# FY_-_OPTO_BOARD_4_IOX.net
KiCad netlist of a schematic drawn in EAGLE
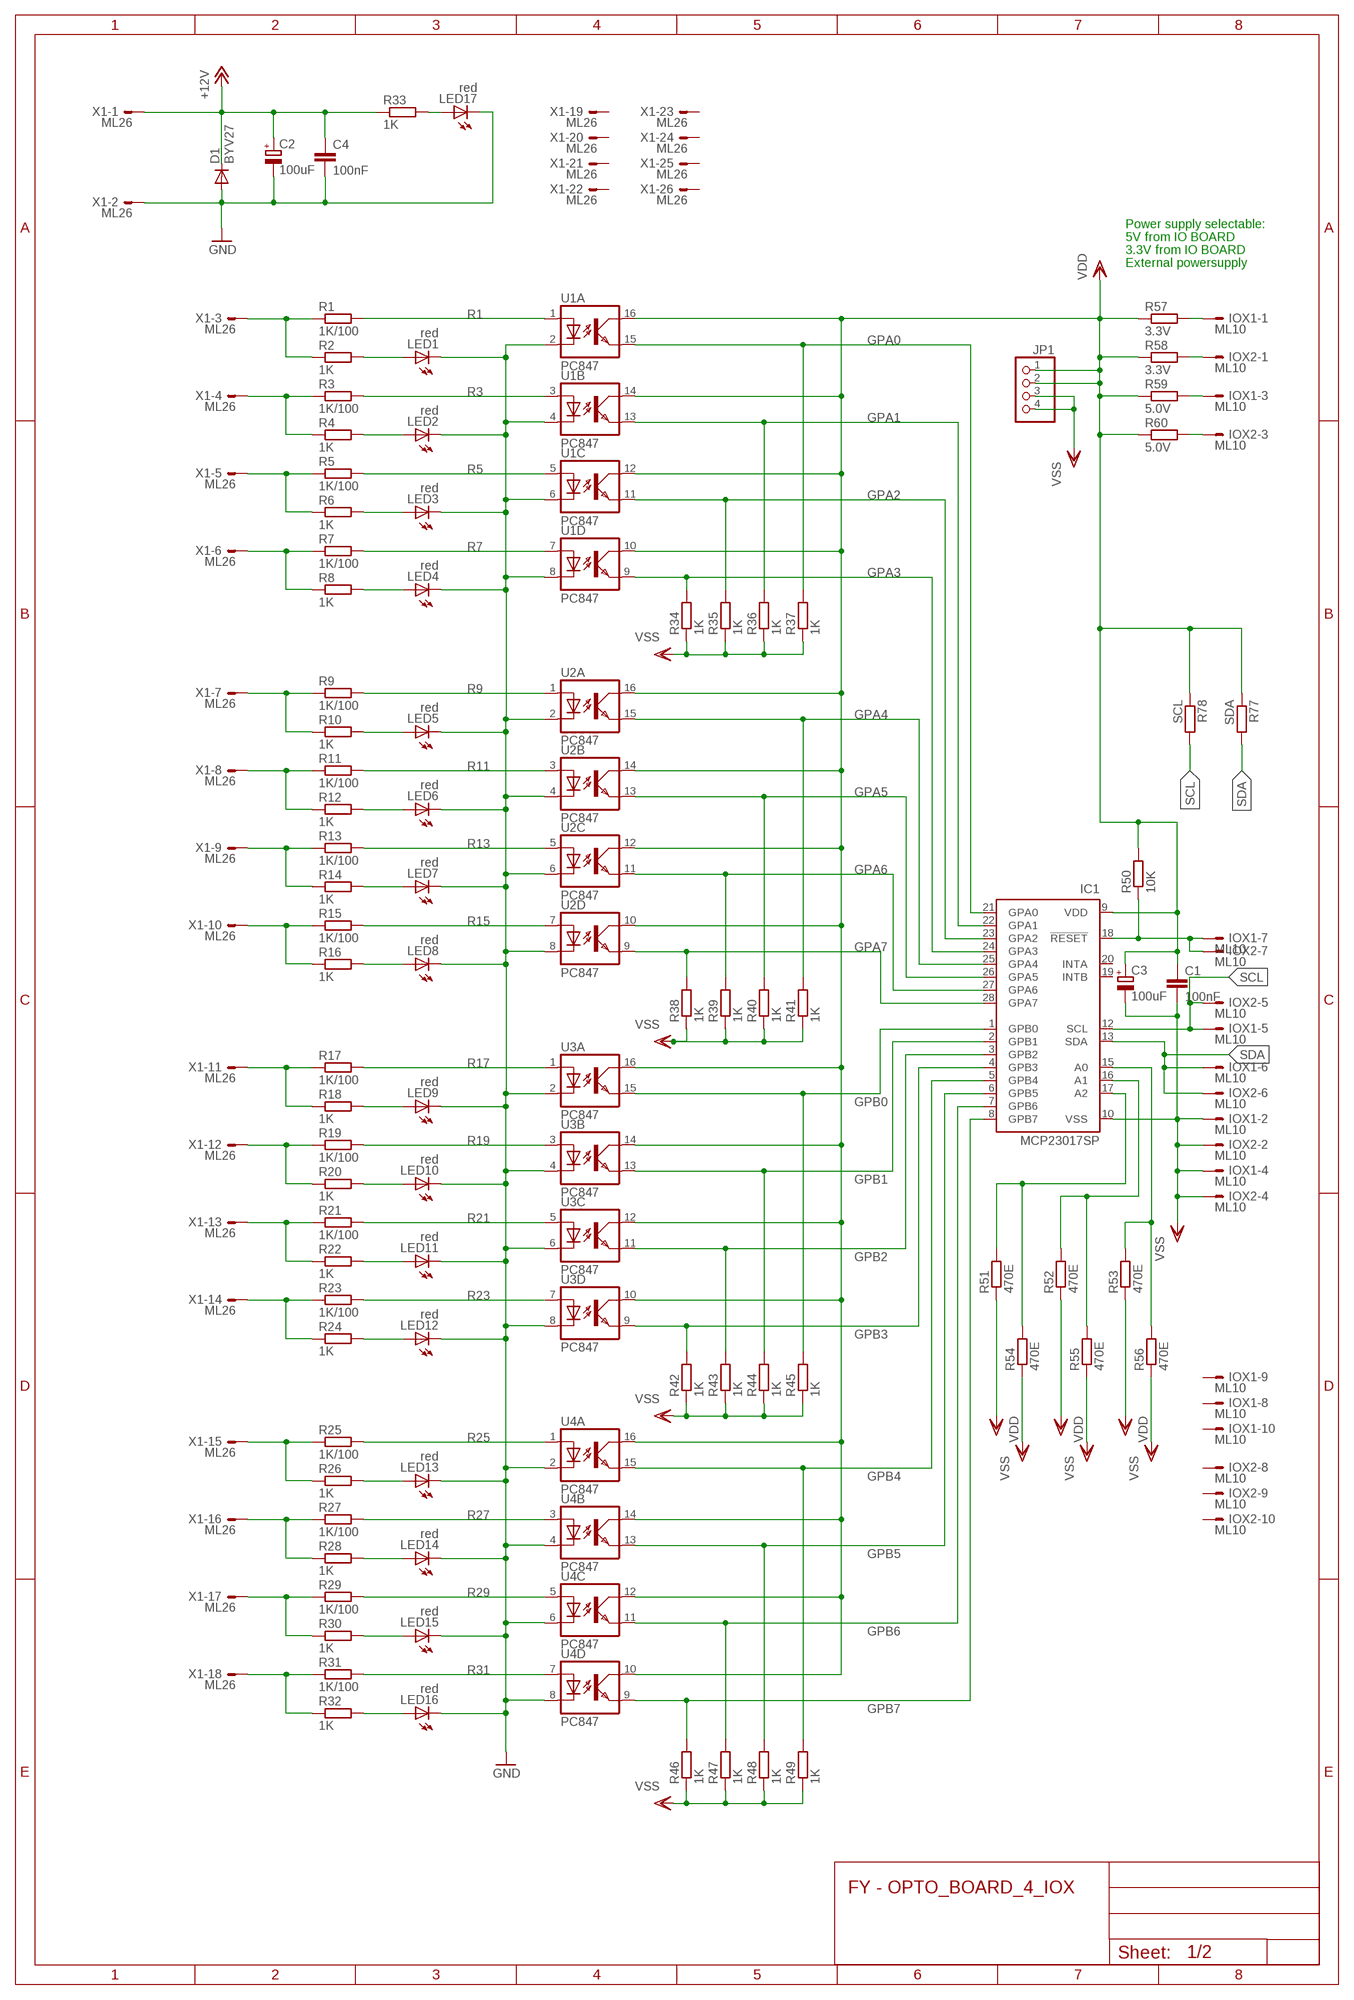
[diagram p0: schematic, sheet 1]
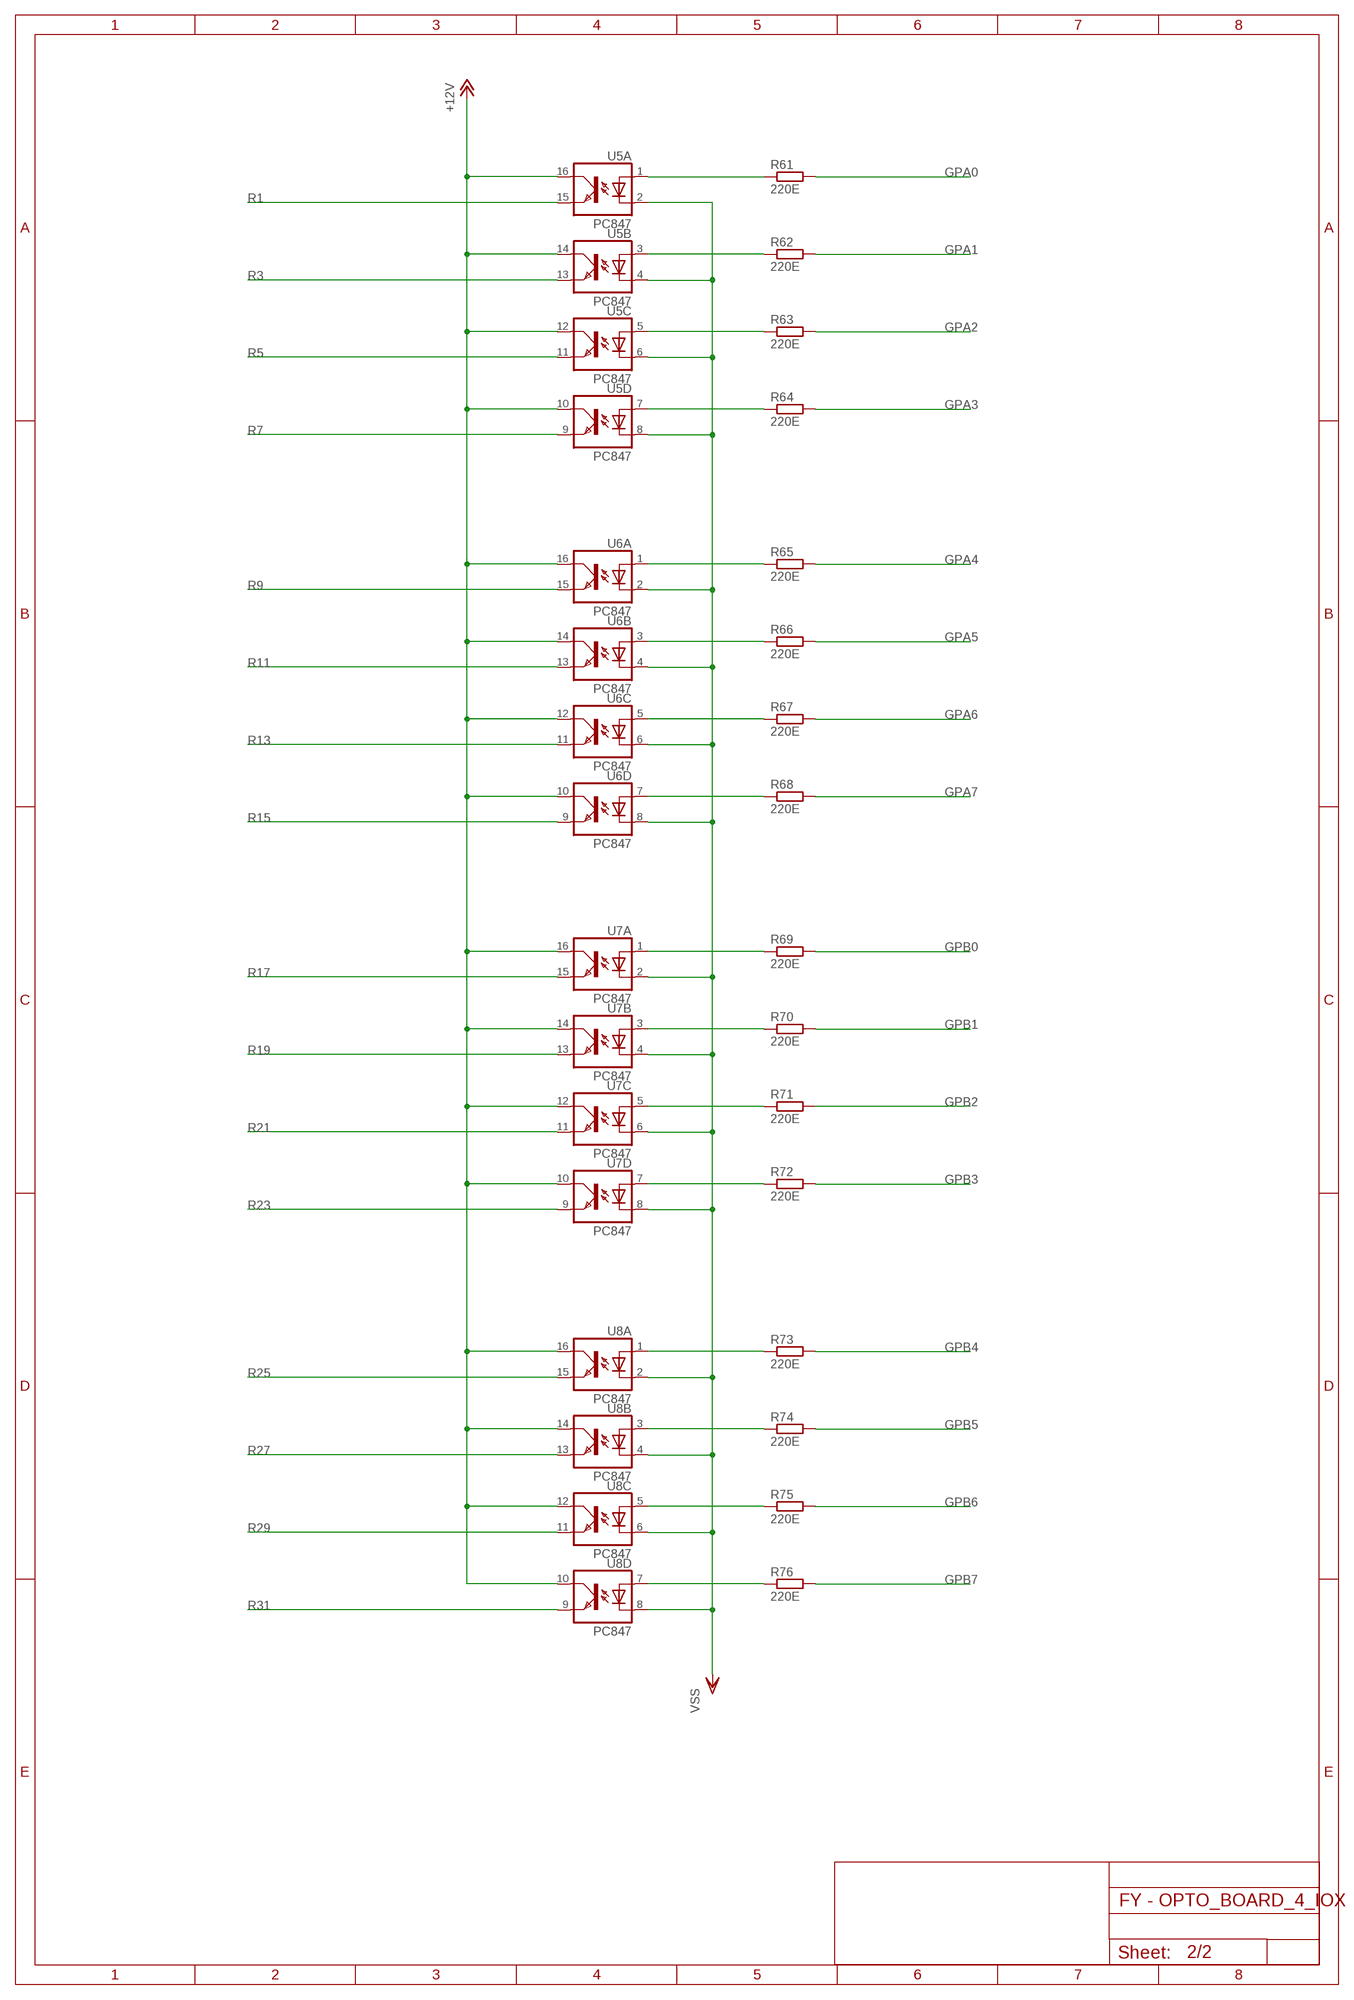
[diagram p1: schematic, sheet 2]

(export (version "E")
  (design (tool "Eeschema 10.0.6"))
  (components
    (comp (ref "R61")
      (value "220E")
      (footprint "eagle-import:0207_10")
      (libsource (lib "eagle-import") (part "R-EU_0207/10"))
    )
    (comp (ref "R62")
      (value "220E")
      (footprint "eagle-import:0207_10")
      (libsource (lib "eagle-import") (part "R-EU_0207/10"))
    )
    (comp (ref "R63")
      (value "220E")
      (footprint "eagle-import:0207_10")
      (libsource (lib "eagle-import") (part "R-EU_0207/10"))
    )
    (comp (ref "R64")
      (value "220E")
      (footprint "eagle-import:0207_10")
      (libsource (lib "eagle-import") (part "R-EU_0207/10"))
    )
    (comp (ref "R65")
      (value "220E")
      (footprint "eagle-import:0207_10")
      (libsource (lib "eagle-import") (part "R-EU_0207/10"))
    )
    (comp (ref "R66")
      (value "220E")
      (footprint "eagle-import:0207_10")
      (libsource (lib "eagle-import") (part "R-EU_0207/10"))
    )
    (comp (ref "R67")
      (value "220E")
      (footprint "eagle-import:0207_10")
      (libsource (lib "eagle-import") (part "R-EU_0207/10"))
    )
    (comp (ref "R68")
      (value "220E")
      (footprint "eagle-import:0207_10")
      (libsource (lib "eagle-import") (part "R-EU_0207/10"))
    )
    (comp (ref "R69")
      (value "220E")
      (footprint "eagle-import:0207_10")
      (libsource (lib "eagle-import") (part "R-EU_0207/10"))
    )
    (comp (ref "R70")
      (value "220E")
      (footprint "eagle-import:0207_10")
      (libsource (lib "eagle-import") (part "R-EU_0207/10"))
    )
    (comp (ref "R71")
      (value "220E")
      (footprint "eagle-import:0207_10")
      (libsource (lib "eagle-import") (part "R-EU_0207/10"))
    )
    (comp (ref "R72")
      (value "220E")
      (footprint "eagle-import:0207_10")
      (libsource (lib "eagle-import") (part "R-EU_0207/10"))
    )
    (comp (ref "R73")
      (value "220E")
      (footprint "eagle-import:0207_10")
      (libsource (lib "eagle-import") (part "R-EU_0207/10"))
    )
    (comp (ref "R74")
      (value "220E")
      (footprint "eagle-import:0207_10")
      (libsource (lib "eagle-import") (part "R-EU_0207/10"))
    )
    (comp (ref "R75")
      (value "220E")
      (footprint "eagle-import:0207_10")
      (libsource (lib "eagle-import") (part "R-EU_0207/10"))
    )
    (comp (ref "R76")
      (value "220E")
      (footprint "eagle-import:0207_10")
      (libsource (lib "eagle-import") (part "R-EU_0207/10"))
    )
    (comp (ref "U5")
      (value "PC847")
      (footprint "eagle-import:DIL16")
      (libsource (lib "eagle-import") (part "PC847"))
    )
    (comp (ref "U6")
      (value "PC847")
      (footprint "eagle-import:DIL16")
      (libsource (lib "eagle-import") (part "PC847"))
    )
    (comp (ref "U7")
      (value "PC847")
      (footprint "eagle-import:DIL16")
      (libsource (lib "eagle-import") (part "PC847"))
    )
    (comp (ref "U8")
      (value "PC847")
      (footprint "eagle-import:DIL16")
      (libsource (lib "eagle-import") (part "PC847"))
    )
    (comp (ref "C1")
      (value "100nF")
      (footprint "eagle-import:C050-025X075")
      (libsource (lib "eagle-import") (part "C-EU050-025X075"))
    )
    (comp (ref "C2")
      (value "100uF")
      (footprint "eagle-import:E5-8,5")
      (libsource (lib "eagle-import") (part "CPOL-EUE5-8.5"))
    )
    (comp (ref "C3")
      (value "100uF")
      (footprint "eagle-import:E5-8,5")
      (libsource (lib "eagle-import") (part "CPOL-EUE5-8.5"))
    )
    (comp (ref "C4")
      (value "100nF")
      (footprint "eagle-import:C050-025X075")
      (libsource (lib "eagle-import") (part "C-EU050-025X075"))
    )
    (comp (ref "D1")
      (value "BYV27")
      (footprint "eagle-import:SOD57-10")
      (libsource (lib "eagle-import") (part "BYV27"))
    )
    (comp (ref "IC1")
      (value "MCP23017SP")
      (footprint "eagle-import:DIL28-3")
      (fields (field (name "MF") "MICROCHIP") (field (name "MPN") "MCP23017-E/SP"))
      (libsource (lib "eagle-import") (part "MCP23017SP"))
    )
    (comp (ref "IOX1")
      (value "ML10")
      (footprint "eagle-import:ML10")
      (libsource (lib "eagle-import") (part "ML10?E"))
    )
    (comp (ref "IOX2")
      (value "ML10")
      (footprint "eagle-import:ML10")
      (libsource (lib "eagle-import") (part "ML10?E"))
    )
    (comp (ref "JP1")
      (value "PINHD-1X4")
      (footprint "eagle-import:1X04")
      (libsource (lib "eagle-import") (part "PINHD-1X4"))
    )
    (comp (ref "LED1")
      (value "red")
      (footprint "eagle-import:LED3MM")
      (libsource (lib "eagle-import") (part "LED3MM"))
    )
    (comp (ref "LED2")
      (value "red")
      (footprint "eagle-import:LED3MM")
      (libsource (lib "eagle-import") (part "LED3MM"))
    )
    (comp (ref "LED3")
      (value "red")
      (footprint "eagle-import:LED3MM")
      (libsource (lib "eagle-import") (part "LED3MM"))
    )
    (comp (ref "LED4")
      (value "red")
      (footprint "eagle-import:LED3MM")
      (libsource (lib "eagle-import") (part "LED3MM"))
    )
    (comp (ref "LED5")
      (value "red")
      (footprint "eagle-import:LED3MM")
      (libsource (lib "eagle-import") (part "LED3MM"))
    )
    (comp (ref "LED6")
      (value "red")
      (footprint "eagle-import:LED3MM")
      (libsource (lib "eagle-import") (part "LED3MM"))
    )
    (comp (ref "LED7")
      (value "red")
      (footprint "eagle-import:LED3MM")
      (libsource (lib "eagle-import") (part "LED3MM"))
    )
    (comp (ref "LED8")
      (value "red")
      (footprint "eagle-import:LED3MM")
      (libsource (lib "eagle-import") (part "LED3MM"))
    )
    (comp (ref "LED9")
      (value "red")
      (footprint "eagle-import:LED3MM")
      (libsource (lib "eagle-import") (part "LED3MM"))
    )
    (comp (ref "LED10")
      (value "red")
      (footprint "eagle-import:LED3MM")
      (libsource (lib "eagle-import") (part "LED3MM"))
    )
    (comp (ref "LED11")
      (value "red")
      (footprint "eagle-import:LED3MM")
      (libsource (lib "eagle-import") (part "LED3MM"))
    )
    (comp (ref "LED12")
      (value "red")
      (footprint "eagle-import:LED3MM")
      (libsource (lib "eagle-import") (part "LED3MM"))
    )
    (comp (ref "LED13")
      (value "red")
      (footprint "eagle-import:LED3MM")
      (libsource (lib "eagle-import") (part "LED3MM"))
    )
    (comp (ref "LED14")
      (value "red")
      (footprint "eagle-import:LED3MM")
      (libsource (lib "eagle-import") (part "LED3MM"))
    )
    (comp (ref "LED15")
      (value "red")
      (footprint "eagle-import:LED3MM")
      (libsource (lib "eagle-import") (part "LED3MM"))
    )
    (comp (ref "LED16")
      (value "red")
      (footprint "eagle-import:LED3MM")
      (libsource (lib "eagle-import") (part "LED3MM"))
    )
    (comp (ref "LED17")
      (value "red")
      (footprint "eagle-import:LED3MM")
      (libsource (lib "eagle-import") (part "LED3MM"))
    )
    (comp (ref "R1")
      (value "1K/100")
      (footprint "eagle-import:0207_10")
      (libsource (lib "eagle-import") (part "R-EU_0207/10"))
    )
    (comp (ref "R2")
      (value "1K")
      (footprint "eagle-import:0207_10")
      (libsource (lib "eagle-import") (part "R-EU_0207/10"))
    )
    (comp (ref "R3")
      (value "1K/100")
      (footprint "eagle-import:0207_10")
      (libsource (lib "eagle-import") (part "R-EU_0207/10"))
    )
    (comp (ref "R4")
      (value "1K")
      (footprint "eagle-import:0207_10")
      (libsource (lib "eagle-import") (part "R-EU_0207/10"))
    )
    (comp (ref "R5")
      (value "1K/100")
      (footprint "eagle-import:0207_10")
      (libsource (lib "eagle-import") (part "R-EU_0207/10"))
    )
    (comp (ref "R6")
      (value "1K")
      (footprint "eagle-import:0207_10")
      (libsource (lib "eagle-import") (part "R-EU_0207/10"))
    )
    (comp (ref "R7")
      (value "1K/100")
      (footprint "eagle-import:0207_10")
      (libsource (lib "eagle-import") (part "R-EU_0207/10"))
    )
    (comp (ref "R8")
      (value "1K")
      (footprint "eagle-import:0207_10")
      (libsource (lib "eagle-import") (part "R-EU_0207/10"))
    )
    (comp (ref "R9")
      (value "1K/100")
      (footprint "eagle-import:0207_10")
      (libsource (lib "eagle-import") (part "R-EU_0207/10"))
    )
    (comp (ref "R10")
      (value "1K")
      (footprint "eagle-import:0207_10")
      (libsource (lib "eagle-import") (part "R-EU_0207/10"))
    )
    (comp (ref "R11")
      (value "1K/100")
      (footprint "eagle-import:0207_10")
      (libsource (lib "eagle-import") (part "R-EU_0207/10"))
    )
    (comp (ref "R12")
      (value "1K")
      (footprint "eagle-import:0207_10")
      (libsource (lib "eagle-import") (part "R-EU_0207/10"))
    )
    (comp (ref "R13")
      (value "1K/100")
      (footprint "eagle-import:0207_10")
      (libsource (lib "eagle-import") (part "R-EU_0207/10"))
    )
    (comp (ref "R14")
      (value "1K")
      (footprint "eagle-import:0207_10")
      (libsource (lib "eagle-import") (part "R-EU_0207/10"))
    )
    (comp (ref "R15")
      (value "1K/100")
      (footprint "eagle-import:0207_10")
      (libsource (lib "eagle-import") (part "R-EU_0207/10"))
    )
    (comp (ref "R16")
      (value "1K")
      (footprint "eagle-import:0207_10")
      (libsource (lib "eagle-import") (part "R-EU_0207/10"))
    )
    (comp (ref "R17")
      (value "1K/100")
      (footprint "eagle-import:0207_10")
      (libsource (lib "eagle-import") (part "R-EU_0207/10"))
    )
    (comp (ref "R18")
      (value "1K")
      (footprint "eagle-import:0207_10")
      (libsource (lib "eagle-import") (part "R-EU_0207/10"))
    )
    (comp (ref "R19")
      (value "1K/100")
      (footprint "eagle-import:0207_10")
      (libsource (lib "eagle-import") (part "R-EU_0207/10"))
    )
    (comp (ref "R20")
      (value "1K")
      (footprint "eagle-import:0207_10")
      (libsource (lib "eagle-import") (part "R-EU_0207/10"))
    )
    (comp (ref "R21")
      (value "1K/100")
      (footprint "eagle-import:0207_10")
      (libsource (lib "eagle-import") (part "R-EU_0207/10"))
    )
    (comp (ref "R22")
      (value "1K")
      (footprint "eagle-import:0207_10")
      (libsource (lib "eagle-import") (part "R-EU_0207/10"))
    )
    (comp (ref "R23")
      (value "1K/100")
      (footprint "eagle-import:0207_10")
      (libsource (lib "eagle-import") (part "R-EU_0207/10"))
    )
    (comp (ref "R24")
      (value "1K")
      (footprint "eagle-import:0207_10")
      (libsource (lib "eagle-import") (part "R-EU_0207/10"))
    )
    (comp (ref "R25")
      (value "1K/100")
      (footprint "eagle-import:0207_10")
      (libsource (lib "eagle-import") (part "R-EU_0207/10"))
    )
    (comp (ref "R26")
      (value "1K")
      (footprint "eagle-import:0207_10")
      (libsource (lib "eagle-import") (part "R-EU_0207/10"))
    )
    (comp (ref "R27")
      (value "1K/100")
      (footprint "eagle-import:0207_10")
      (libsource (lib "eagle-import") (part "R-EU_0207/10"))
    )
    (comp (ref "R28")
      (value "1K")
      (footprint "eagle-import:0207_10")
      (libsource (lib "eagle-import") (part "R-EU_0207/10"))
    )
    (comp (ref "R29")
      (value "1K/100")
      (footprint "eagle-import:0207_10")
      (libsource (lib "eagle-import") (part "R-EU_0207/10"))
    )
    (comp (ref "R30")
      (value "1K")
      (footprint "eagle-import:0207_10")
      (libsource (lib "eagle-import") (part "R-EU_0207/10"))
    )
    (comp (ref "R31")
      (value "1K/100")
      (footprint "eagle-import:0207_10")
      (libsource (lib "eagle-import") (part "R-EU_0207/10"))
    )
    (comp (ref "R32")
      (value "1K")
      (footprint "eagle-import:0207_10")
      (libsource (lib "eagle-import") (part "R-EU_0207/10"))
    )
    (comp (ref "R33")
      (value "1K")
      (footprint "eagle-import:0207_10")
      (libsource (lib "eagle-import") (part "R-EU_0207/10"))
    )
    (comp (ref "R34")
      (value "1K")
      (footprint "eagle-import:0207_10")
      (libsource (lib "eagle-import") (part "R-EU_0207/10"))
    )
    (comp (ref "R35")
      (value "1K")
      (footprint "eagle-import:0207_10")
      (libsource (lib "eagle-import") (part "R-EU_0207/10"))
    )
    (comp (ref "R36")
      (value "1K")
      (footprint "eagle-import:0207_10")
      (libsource (lib "eagle-import") (part "R-EU_0207/10"))
    )
    (comp (ref "R37")
      (value "1K")
      (footprint "eagle-import:0207_10")
      (libsource (lib "eagle-import") (part "R-EU_0207/10"))
    )
    (comp (ref "R38")
      (value "1K")
      (footprint "eagle-import:0207_10")
      (libsource (lib "eagle-import") (part "R-EU_0207/10"))
    )
    (comp (ref "R39")
      (value "1K")
      (footprint "eagle-import:0207_10")
      (libsource (lib "eagle-import") (part "R-EU_0207/10"))
    )
    (comp (ref "R40")
      (value "1K")
      (footprint "eagle-import:0207_10")
      (libsource (lib "eagle-import") (part "R-EU_0207/10"))
    )
    (comp (ref "R41")
      (value "1K")
      (footprint "eagle-import:0207_10")
      (libsource (lib "eagle-import") (part "R-EU_0207/10"))
    )
    (comp (ref "R42")
      (value "1K")
      (footprint "eagle-import:0207_10")
      (libsource (lib "eagle-import") (part "R-EU_0207/10"))
    )
    (comp (ref "R43")
      (value "1K")
      (footprint "eagle-import:0207_10")
      (libsource (lib "eagle-import") (part "R-EU_0207/10"))
    )
    (comp (ref "R44")
      (value "1K")
      (footprint "eagle-import:0207_10")
      (libsource (lib "eagle-import") (part "R-EU_0207/10"))
    )
    (comp (ref "R45")
      (value "1K")
      (footprint "eagle-import:0207_10")
      (libsource (lib "eagle-import") (part "R-EU_0207/10"))
    )
    (comp (ref "R46")
      (value "1K")
      (footprint "eagle-import:0207_10")
      (libsource (lib "eagle-import") (part "R-EU_0207/10"))
    )
    (comp (ref "R47")
      (value "1K")
      (footprint "eagle-import:0207_10")
      (libsource (lib "eagle-import") (part "R-EU_0207/10"))
    )
    (comp (ref "R48")
      (value "1K")
      (footprint "eagle-import:0207_10")
      (libsource (lib "eagle-import") (part "R-EU_0207/10"))
    )
    (comp (ref "R49")
      (value "1K")
      (footprint "eagle-import:0207_10")
      (libsource (lib "eagle-import") (part "R-EU_0207/10"))
    )
    (comp (ref "R50")
      (value "10K")
      (footprint "eagle-import:0207_10")
      (libsource (lib "eagle-import") (part "R-EU_0207/10"))
    )
    (comp (ref "R51")
      (value "470E")
      (footprint "eagle-import:0207_10")
      (libsource (lib "eagle-import") (part "R-EU_0207/10"))
    )
    (comp (ref "R52")
      (value "470E")
      (footprint "eagle-import:0207_10")
      (libsource (lib "eagle-import") (part "R-EU_0207/10"))
    )
    (comp (ref "R53")
      (value "470E")
      (footprint "eagle-import:0207_10")
      (libsource (lib "eagle-import") (part "R-EU_0207/10"))
    )
    (comp (ref "R54")
      (value "470E")
      (footprint "eagle-import:0207_10")
      (libsource (lib "eagle-import") (part "R-EU_0207/10"))
    )
    (comp (ref "R55")
      (value "470E")
      (footprint "eagle-import:0207_10")
      (libsource (lib "eagle-import") (part "R-EU_0207/10"))
    )
    (comp (ref "R56")
      (value "470E")
      (footprint "eagle-import:0207_10")
      (libsource (lib "eagle-import") (part "R-EU_0207/10"))
    )
    (comp (ref "R57")
      (value "3.3V")
      (footprint "eagle-import:0204V")
      (libsource (lib "eagle-import") (part "R-EU_0204/2V"))
    )
    (comp (ref "R58")
      (value "3.3V")
      (footprint "eagle-import:0204V")
      (libsource (lib "eagle-import") (part "R-EU_0204/2V"))
    )
    (comp (ref "R59")
      (value "5.0V")
      (footprint "eagle-import:0204V")
      (libsource (lib "eagle-import") (part "R-EU_0204/2V"))
    )
    (comp (ref "R60")
      (value "5.0V")
      (footprint "eagle-import:0204V")
      (libsource (lib "eagle-import") (part "R-EU_0204/2V"))
    )
    (comp (ref "R77")
      (value "SDA")
      (footprint "eagle-import:0207_10")
      (libsource (lib "eagle-import") (part "R-EU_0207/10"))
    )
    (comp (ref "R78")
      (value "SCL")
      (footprint "eagle-import:0207_10")
      (libsource (lib "eagle-import") (part "R-EU_0207/10"))
    )
    (comp (ref "U1")
      (value "PC847")
      (footprint "eagle-import:DIL16")
      (libsource (lib "eagle-import") (part "PC847"))
    )
    (comp (ref "U2")
      (value "PC847")
      (footprint "eagle-import:DIL16")
      (libsource (lib "eagle-import") (part "PC847"))
    )
    (comp (ref "U3")
      (value "PC847")
      (footprint "eagle-import:DIL16")
      (libsource (lib "eagle-import") (part "PC847"))
    )
    (comp (ref "U4")
      (value "PC847")
      (footprint "eagle-import:DIL16")
      (libsource (lib "eagle-import") (part "PC847"))
    )
    (comp (ref "X1")
      (value "ML26")
      (footprint "eagle-import:ML26")
      (libsource (lib "eagle-import") (part "ML26?E"))
    )
  )
  (nets
    (net (code "1") (name "+12V") (class "Default")
      (node (ref "C2") (pin "+") (pinfunction "+_+") (pintype "passive"))
      (node (ref "C4") (pin "1") (pinfunction "1_1") (pintype "passive"))
      (node (ref "D1") (pin "C") (pinfunction "C_C") (pintype "passive"))
      (node (ref "R33") (pin "1") (pinfunction "1_1") (pintype "passive"))
      (node (ref "U5") (pin "10") (pinfunction "COL_10") (pintype "passive"))
      (node (ref "U5") (pin "12") (pinfunction "COL_12") (pintype "passive"))
      (node (ref "U5") (pin "14") (pinfunction "COL_14") (pintype "passive"))
      (node (ref "U5") (pin "16") (pinfunction "COL_16") (pintype "passive"))
      (node (ref "U6") (pin "10") (pinfunction "COL_10") (pintype "passive"))
      (node (ref "U6") (pin "12") (pinfunction "COL_12") (pintype "passive"))
      (node (ref "U6") (pin "14") (pinfunction "COL_14") (pintype "passive"))
      (node (ref "U6") (pin "16") (pinfunction "COL_16") (pintype "passive"))
      (node (ref "U7") (pin "10") (pinfunction "COL_10") (pintype "passive"))
      (node (ref "U7") (pin "12") (pinfunction "COL_12") (pintype "passive"))
      (node (ref "U7") (pin "14") (pinfunction "COL_14") (pintype "passive"))
      (node (ref "U7") (pin "16") (pinfunction "COL_16") (pintype "passive"))
      (node (ref "U8") (pin "10") (pinfunction "COL_10") (pintype "passive"))
      (node (ref "U8") (pin "12") (pinfunction "COL_12") (pintype "passive"))
      (node (ref "U8") (pin "14") (pinfunction "COL_14") (pintype "passive"))
      (node (ref "U8") (pin "16") (pinfunction "COL_16") (pintype "passive"))
      (node (ref "X1") (pin "1") (pinfunction "S_1") (pintype "passive"))
    )
    (net (code "2") (name "GND") (class "Default")
      (node (ref "C2") (pin "-") (pinfunction "-_-") (pintype "passive"))
      (node (ref "C4") (pin "2") (pinfunction "2_2") (pintype "passive"))
      (node (ref "D1") (pin "A") (pinfunction "A_A") (pintype "passive"))
      (node (ref "LED1") (pin "K") (pinfunction "C_K") (pintype "passive"))
      (node (ref "LED10") (pin "K") (pinfunction "C_K") (pintype "passive"))
      (node (ref "LED11") (pin "K") (pinfunction "C_K") (pintype "passive"))
      (node (ref "LED12") (pin "K") (pinfunction "C_K") (pintype "passive"))
      (node (ref "LED13") (pin "K") (pinfunction "C_K") (pintype "passive"))
      (node (ref "LED14") (pin "K") (pinfunction "C_K") (pintype "passive"))
      (node (ref "LED15") (pin "K") (pinfunction "C_K") (pintype "passive"))
      (node (ref "LED16") (pin "K") (pinfunction "C_K") (pintype "passive"))
      (node (ref "LED17") (pin "K") (pinfunction "C_K") (pintype "passive"))
      (node (ref "LED2") (pin "K") (pinfunction "C_K") (pintype "passive"))
      (node (ref "LED3") (pin "K") (pinfunction "C_K") (pintype "passive"))
      (node (ref "LED4") (pin "K") (pinfunction "C_K") (pintype "passive"))
      (node (ref "LED5") (pin "K") (pinfunction "C_K") (pintype "passive"))
      (node (ref "LED6") (pin "K") (pinfunction "C_K") (pintype "passive"))
      (node (ref "LED7") (pin "K") (pinfunction "C_K") (pintype "passive"))
      (node (ref "LED8") (pin "K") (pinfunction "C_K") (pintype "passive"))
      (node (ref "LED9") (pin "K") (pinfunction "C_K") (pintype "passive"))
      (node (ref "U1") (pin "2") (pinfunction "C_2") (pintype "passive"))
      (node (ref "U1") (pin "4") (pinfunction "C_4") (pintype "passive"))
      (node (ref "U1") (pin "6") (pinfunction "C_6") (pintype "passive"))
      (node (ref "U1") (pin "8") (pinfunction "C_8") (pintype "passive"))
      (node (ref "U2") (pin "2") (pinfunction "C_2") (pintype "passive"))
      (node (ref "U2") (pin "4") (pinfunction "C_4") (pintype "passive"))
      (node (ref "U2") (pin "6") (pinfunction "C_6") (pintype "passive"))
      (node (ref "U2") (pin "8") (pinfunction "C_8") (pintype "passive"))
      (node (ref "U3") (pin "2") (pinfunction "C_2") (pintype "passive"))
      (node (ref "U3") (pin "4") (pinfunction "C_4") (pintype "passive"))
      (node (ref "U3") (pin "6") (pinfunction "C_6") (pintype "passive"))
      (node (ref "U3") (pin "8") (pinfunction "C_8") (pintype "passive"))
      (node (ref "U4") (pin "2") (pinfunction "C_2") (pintype "passive"))
      (node (ref "U4") (pin "4") (pinfunction "C_4") (pintype "passive"))
      (node (ref "U4") (pin "6") (pinfunction "C_6") (pintype "passive"))
      (node (ref "U4") (pin "8") (pinfunction "C_8") (pintype "passive"))
      (node (ref "X1") (pin "2") (pinfunction "S_2") (pintype "passive"))
    )
    (net (code "3") (name "GPA0") (class "Default")
      (node (ref "IC1") (pin "21") (pinfunction "GPA0_21") (pintype "bidirectional"))
      (node (ref "R37") (pin "2") (pinfunction "2_2") (pintype "passive"))
      (node (ref "R61") (pin "2") (pinfunction "2_2") (pintype "passive"))
      (node (ref "U1") (pin "15") (pinfunction "EMIT_15") (pintype "passive"))
    )
    (net (code "4") (name "GPA1") (class "Default")
      (node (ref "IC1") (pin "22") (pinfunction "GPA1_22") (pintype "bidirectional"))
      (node (ref "R36") (pin "2") (pinfunction "2_2") (pintype "passive"))
      (node (ref "R62") (pin "2") (pinfunction "2_2") (pintype "passive"))
      (node (ref "U1") (pin "13") (pinfunction "EMIT_13") (pintype "passive"))
    )
    (net (code "5") (name "GPA2") (class "Default")
      (node (ref "IC1") (pin "23") (pinfunction "GPA2_23") (pintype "bidirectional"))
      (node (ref "R35") (pin "2") (pinfunction "2_2") (pintype "passive"))
      (node (ref "R63") (pin "2") (pinfunction "2_2") (pintype "passive"))
      (node (ref "U1") (pin "11") (pinfunction "EMIT_11") (pintype "passive"))
    )
    (net (code "6") (name "GPA3") (class "Default")
      (node (ref "IC1") (pin "24") (pinfunction "GPA3_24") (pintype "bidirectional"))
      (node (ref "R34") (pin "2") (pinfunction "2_2") (pintype "passive"))
      (node (ref "R64") (pin "2") (pinfunction "2_2") (pintype "passive"))
      (node (ref "U1") (pin "9") (pinfunction "EMIT_9") (pintype "passive"))
    )
    (net (code "7") (name "GPA4") (class "Default")
      (node (ref "IC1") (pin "25") (pinfunction "GPA4_25") (pintype "bidirectional"))
      (node (ref "R41") (pin "2") (pinfunction "2_2") (pintype "passive"))
      (node (ref "R65") (pin "2") (pinfunction "2_2") (pintype "passive"))
      (node (ref "U2") (pin "15") (pinfunction "EMIT_15") (pintype "passive"))
    )
    (net (code "8") (name "GPA5") (class "Default")
      (node (ref "IC1") (pin "26") (pinfunction "GPA5_26") (pintype "bidirectional"))
      (node (ref "R40") (pin "2") (pinfunction "2_2") (pintype "passive"))
      (node (ref "R66") (pin "2") (pinfunction "2_2") (pintype "passive"))
      (node (ref "U2") (pin "13") (pinfunction "EMIT_13") (pintype "passive"))
    )
    (net (code "9") (name "GPA6") (class "Default")
      (node (ref "IC1") (pin "27") (pinfunction "GPA6_27") (pintype "bidirectional"))
      (node (ref "R39") (pin "2") (pinfunction "2_2") (pintype "passive"))
      (node (ref "R67") (pin "2") (pinfunction "2_2") (pintype "passive"))
      (node (ref "U2") (pin "11") (pinfunction "EMIT_11") (pintype "passive"))
    )
    (net (code "10") (name "GPA7") (class "Default")
      (node (ref "IC1") (pin "28") (pinfunction "GPA7_28") (pintype "bidirectional"))
      (node (ref "R38") (pin "2") (pinfunction "2_2") (pintype "passive"))
      (node (ref "R68") (pin "2") (pinfunction "2_2") (pintype "passive"))
      (node (ref "U2") (pin "9") (pinfunction "EMIT_9") (pintype "passive"))
    )
    (net (code "11") (name "GPB0") (class "Default")
      (node (ref "IC1") (pin "1") (pinfunction "GPB0_1") (pintype "bidirectional"))
      (node (ref "R45") (pin "2") (pinfunction "2_2") (pintype "passive"))
      (node (ref "R69") (pin "2") (pinfunction "2_2") (pintype "passive"))
      (node (ref "U3") (pin "15") (pinfunction "EMIT_15") (pintype "passive"))
    )
    (net (code "12") (name "GPB1") (class "Default")
      (node (ref "IC1") (pin "2") (pinfunction "GPB1_2") (pintype "bidirectional"))
      (node (ref "R44") (pin "2") (pinfunction "2_2") (pintype "passive"))
      (node (ref "R70") (pin "2") (pinfunction "2_2") (pintype "passive"))
      (node (ref "U3") (pin "13") (pinfunction "EMIT_13") (pintype "passive"))
    )
    (net (code "13") (name "GPB2") (class "Default")
      (node (ref "IC1") (pin "3") (pinfunction "GPB2_3") (pintype "bidirectional"))
      (node (ref "R43") (pin "2") (pinfunction "2_2") (pintype "passive"))
      (node (ref "R71") (pin "2") (pinfunction "2_2") (pintype "passive"))
      (node (ref "U3") (pin "11") (pinfunction "EMIT_11") (pintype "passive"))
    )
    (net (code "14") (name "GPB3") (class "Default")
      (node (ref "IC1") (pin "4") (pinfunction "GPB3_4") (pintype "bidirectional"))
      (node (ref "R42") (pin "2") (pinfunction "2_2") (pintype "passive"))
      (node (ref "R72") (pin "2") (pinfunction "2_2") (pintype "passive"))
      (node (ref "U3") (pin "9") (pinfunction "EMIT_9") (pintype "passive"))
    )
    (net (code "15") (name "GPB4") (class "Default")
      (node (ref "IC1") (pin "5") (pinfunction "GPB4_5") (pintype "bidirectional"))
      (node (ref "R49") (pin "2") (pinfunction "2_2") (pintype "passive"))
      (node (ref "R73") (pin "2") (pinfunction "2_2") (pintype "passive"))
      (node (ref "U4") (pin "15") (pinfunction "EMIT_15") (pintype "passive"))
    )
    (net (code "16") (name "GPB5") (class "Default")
      (node (ref "IC1") (pin "6") (pinfunction "GPB5_6") (pintype "bidirectional"))
      (node (ref "R48") (pin "2") (pinfunction "2_2") (pintype "passive"))
      (node (ref "R74") (pin "2") (pinfunction "2_2") (pintype "passive"))
      (node (ref "U4") (pin "13") (pinfunction "EMIT_13") (pintype "passive"))
    )
    (net (code "17") (name "GPB6") (class "Default")
      (node (ref "IC1") (pin "7") (pinfunction "GPB6_7") (pintype "bidirectional"))
      (node (ref "R47") (pin "2") (pinfunction "2_2") (pintype "passive"))
      (node (ref "R75") (pin "2") (pinfunction "2_2") (pintype "passive"))
      (node (ref "U4") (pin "11") (pinfunction "EMIT_11") (pintype "passive"))
    )
    (net (code "18") (name "GPB7") (class "Default")
      (node (ref "IC1") (pin "8") (pinfunction "GPB7_8") (pintype "bidirectional"))
      (node (ref "R46") (pin "2") (pinfunction "2_2") (pintype "passive"))
      (node (ref "R76") (pin "2") (pinfunction "2_2") (pintype "passive"))
      (node (ref "U4") (pin "9") (pinfunction "EMIT_9") (pintype "passive"))
    )
    (net (code "19") (name "Net-(IC1-A0)") (class "Default")
      (node (ref "IC1") (pin "15") (pinfunction "A0_15") (pintype "input"))
      (node (ref "R53") (pin "2") (pinfunction "2_2") (pintype "passive"))
      (node (ref "R56") (pin "2") (pinfunction "2_2") (pintype "passive"))
    )
    (net (code "20") (name "Net-(IC1-A1)") (class "Default")
      (node (ref "IC1") (pin "16") (pinfunction "A1_16") (pintype "input"))
      (node (ref "R52") (pin "2") (pinfunction "2_2") (pintype "passive"))
      (node (ref "R55") (pin "2") (pinfunction "2_2") (pintype "passive"))
    )
    (net (code "21") (name "Net-(IC1-A2)") (class "Default")
      (node (ref "IC1") (pin "17") (pinfunction "A2_17") (pintype "input"))
      (node (ref "R51") (pin "2") (pinfunction "2_2") (pintype "passive"))
      (node (ref "R54") (pin "2") (pinfunction "2_2") (pintype "passive"))
    )
    (net (code "22") (name "Net-(IC1-~{RESET})") (class "Default")
      (node (ref "IC1") (pin "18") (pinfunction "~{RESET}_18") (pintype "input"))
      (node (ref "IOX1") (pin "7") (pinfunction "S_7") (pintype "passive"))
      (node (ref "IOX2") (pin "7") (pinfunction "S_7") (pintype "passive"))
      (node (ref "R50") (pin "1") (pinfunction "1_1") (pintype "passive"))
    )
    (net (code "23") (name "Net-(IOX1A-S)") (class "Default")
      (node (ref "IOX1") (pin "1") (pinfunction "S_1") (pintype "passive"))
      (node (ref "R57") (pin "2") (pinfunction "2_2") (pintype "passive"))
    )
    (net (code "24") (name "Net-(IOX1D-S)") (class "Default")
      (node (ref "IOX1") (pin "3") (pinfunction "S_3") (pintype "passive"))
      (node (ref "R59") (pin "2") (pinfunction "2_2") (pintype "passive"))
    )
    (net (code "25") (name "Net-(IOX2A-S)") (class "Default")
      (node (ref "IOX2") (pin "1") (pinfunction "S_1") (pintype "passive"))
      (node (ref "R58") (pin "2") (pinfunction "2_2") (pintype "passive"))
    )
    (net (code "26") (name "Net-(IOX2D-S)") (class "Default")
      (node (ref "IOX2") (pin "3") (pinfunction "S_3") (pintype "passive"))
      (node (ref "R60") (pin "2") (pinfunction "2_2") (pintype "passive"))
    )
    (net (code "27") (name "Net-(LED1-PadA)") (class "Default")
      (node (ref "LED1") (pin "A") (pinfunction "A_A") (pintype "passive"))
      (node (ref "R2") (pin "2") (pinfunction "2_2") (pintype "passive"))
    )
    (net (code "28") (name "Net-(LED2-PadA)") (class "Default")
      (node (ref "LED2") (pin "A") (pinfunction "A_A") (pintype "passive"))
      (node (ref "R4") (pin "2") (pinfunction "2_2") (pintype "passive"))
    )
    (net (code "29") (name "Net-(LED3-PadA)") (class "Default")
      (node (ref "LED3") (pin "A") (pinfunction "A_A") (pintype "passive"))
      (node (ref "R6") (pin "2") (pinfunction "2_2") (pintype "passive"))
    )
    (net (code "30") (name "Net-(LED4-PadA)") (class "Default")
      (node (ref "LED4") (pin "A") (pinfunction "A_A") (pintype "passive"))
      (node (ref "R8") (pin "2") (pinfunction "2_2") (pintype "passive"))
    )
    (net (code "31") (name "Net-(LED5-PadA)") (class "Default")
      (node (ref "LED5") (pin "A") (pinfunction "A_A") (pintype "passive"))
      (node (ref "R10") (pin "2") (pinfunction "2_2") (pintype "passive"))
    )
    (net (code "32") (name "Net-(LED6-PadA)") (class "Default")
      (node (ref "LED6") (pin "A") (pinfunction "A_A") (pintype "passive"))
      (node (ref "R12") (pin "2") (pinfunction "2_2") (pintype "passive"))
    )
    (net (code "33") (name "Net-(LED7-PadA)") (class "Default")
      (node (ref "LED7") (pin "A") (pinfunction "A_A") (pintype "passive"))
      (node (ref "R14") (pin "2") (pinfunction "2_2") (pintype "passive"))
    )
    (net (code "34") (name "Net-(LED8-PadA)") (class "Default")
      (node (ref "LED8") (pin "A") (pinfunction "A_A") (pintype "passive"))
      (node (ref "R16") (pin "2") (pinfunction "2_2") (pintype "passive"))
    )
    (net (code "35") (name "Net-(LED9-PadA)") (class "Default")
      (node (ref "LED9") (pin "A") (pinfunction "A_A") (pintype "passive"))
      (node (ref "R18") (pin "2") (pinfunction "2_2") (pintype "passive"))
    )
    (net (code "36") (name "Net-(LED10-PadA)") (class "Default")
      (node (ref "LED10") (pin "A") (pinfunction "A_A") (pintype "passive"))
      (node (ref "R20") (pin "2") (pinfunction "2_2") (pintype "passive"))
    )
    (net (code "37") (name "Net-(LED11-PadA)") (class "Default")
      (node (ref "LED11") (pin "A") (pinfunction "A_A") (pintype "passive"))
      (node (ref "R22") (pin "2") (pinfunction "2_2") (pintype "passive"))
    )
    (net (code "38") (name "Net-(LED12-PadA)") (class "Default")
      (node (ref "LED12") (pin "A") (pinfunction "A_A") (pintype "passive"))
      (node (ref "R24") (pin "2") (pinfunction "2_2") (pintype "passive"))
    )
    (net (code "39") (name "Net-(LED13-PadA)") (class "Default")
      (node (ref "LED13") (pin "A") (pinfunction "A_A") (pintype "passive"))
      (node (ref "R26") (pin "2") (pinfunction "2_2") (pintype "passive"))
    )
    (net (code "40") (name "Net-(LED14-PadA)") (class "Default")
      (node (ref "LED14") (pin "A") (pinfunction "A_A") (pintype "passive"))
      (node (ref "R28") (pin "2") (pinfunction "2_2") (pintype "passive"))
    )
    (net (code "41") (name "Net-(LED15-PadA)") (class "Default")
      (node (ref "LED15") (pin "A") (pinfunction "A_A") (pintype "passive"))
      (node (ref "R30") (pin "2") (pinfunction "2_2") (pintype "passive"))
    )
    (net (code "42") (name "Net-(LED16-PadA)") (class "Default")
      (node (ref "LED16") (pin "A") (pinfunction "A_A") (pintype "passive"))
      (node (ref "R32") (pin "2") (pinfunction "2_2") (pintype "passive"))
    )
    (net (code "43") (name "Net-(LED17-PadA)") (class "Default")
      (node (ref "LED17") (pin "A") (pinfunction "A_A") (pintype "passive"))
      (node (ref "R33") (pin "2") (pinfunction "2_2") (pintype "passive"))
    )
    (net (code "44") (name "Net-(U5A-A)") (class "Default")
      (node (ref "R61") (pin "1") (pinfunction "1_1") (pintype "passive"))
      (node (ref "U5") (pin "1") (pinfunction "A_1") (pintype "passive"))
    )
    (net (code "45") (name "Net-(U5B-A)") (class "Default")
      (node (ref "R62") (pin "1") (pinfunction "1_1") (pintype "passive"))
      (node (ref "U5") (pin "3") (pinfunction "A_3") (pintype "passive"))
    )
    (net (code "46") (name "Net-(U5C-A)") (class "Default")
      (node (ref "R63") (pin "1") (pinfunction "1_1") (pintype "passive"))
      (node (ref "U5") (pin "5") (pinfunction "A_5") (pintype "passive"))
    )
    (net (code "47") (name "Net-(U5D-A)") (class "Default")
      (node (ref "R64") (pin "1") (pinfunction "1_1") (pintype "passive"))
      (node (ref "U5") (pin "7") (pinfunction "A_7") (pintype "passive"))
    )
    (net (code "48") (name "Net-(U6A-A)") (class "Default")
      (node (ref "R65") (pin "1") (pinfunction "1_1") (pintype "passive"))
      (node (ref "U6") (pin "1") (pinfunction "A_1") (pintype "passive"))
    )
    (net (code "49") (name "Net-(U6B-A)") (class "Default")
      (node (ref "R66") (pin "1") (pinfunction "1_1") (pintype "passive"))
      (node (ref "U6") (pin "3") (pinfunction "A_3") (pintype "passive"))
    )
    (net (code "50") (name "Net-(U6C-A)") (class "Default")
      (node (ref "R67") (pin "1") (pinfunction "1_1") (pintype "passive"))
      (node (ref "U6") (pin "5") (pinfunction "A_5") (pintype "passive"))
    )
    (net (code "51") (name "Net-(U6D-A)") (class "Default")
      (node (ref "R68") (pin "1") (pinfunction "1_1") (pintype "passive"))
      (node (ref "U6") (pin "7") (pinfunction "A_7") (pintype "passive"))
    )
    (net (code "52") (name "Net-(U7A-A)") (class "Default")
      (node (ref "R69") (pin "1") (pinfunction "1_1") (pintype "passive"))
      (node (ref "U7") (pin "1") (pinfunction "A_1") (pintype "passive"))
    )
    (net (code "53") (name "Net-(U7B-A)") (class "Default")
      (node (ref "R70") (pin "1") (pinfunction "1_1") (pintype "passive"))
      (node (ref "U7") (pin "3") (pinfunction "A_3") (pintype "passive"))
    )
    (net (code "54") (name "Net-(U7C-A)") (class "Default")
      (node (ref "R71") (pin "1") (pinfunction "1_1") (pintype "passive"))
      (node (ref "U7") (pin "5") (pinfunction "A_5") (pintype "passive"))
    )
    (net (code "55") (name "Net-(U7D-A)") (class "Default")
      (node (ref "R72") (pin "1") (pinfunction "1_1") (pintype "passive"))
      (node (ref "U7") (pin "7") (pinfunction "A_7") (pintype "passive"))
    )
    (net (code "56") (name "Net-(U8A-A)") (class "Default")
      (node (ref "R73") (pin "1") (pinfunction "1_1") (pintype "passive"))
      (node (ref "U8") (pin "1") (pinfunction "A_1") (pintype "passive"))
    )
    (net (code "57") (name "Net-(U8B-A)") (class "Default")
      (node (ref "R74") (pin "1") (pinfunction "1_1") (pintype "passive"))
      (node (ref "U8") (pin "3") (pinfunction "A_3") (pintype "passive"))
    )
    (net (code "58") (name "Net-(U8C-A)") (class "Default")
      (node (ref "R75") (pin "1") (pinfunction "1_1") (pintype "passive"))
      (node (ref "U8") (pin "5") (pinfunction "A_5") (pintype "passive"))
    )
    (net (code "59") (name "Net-(U8D-A)") (class "Default")
      (node (ref "R76") (pin "1") (pinfunction "1_1") (pintype "passive"))
      (node (ref "U8") (pin "7") (pinfunction "A_7") (pintype "passive"))
    )
    (net (code "60") (name "Net-(X1B-S)") (class "Default")
      (node (ref "R15") (pin "1") (pinfunction "1_1") (pintype "passive"))
      (node (ref "R16") (pin "1") (pinfunction "1_1") (pintype "passive"))
      (node (ref "X1") (pin "10") (pinfunction "S_10") (pintype "passive"))
    )
    (net (code "61") (name "Net-(X1C-S)") (class "Default")
      (node (ref "R17") (pin "1") (pinfunction "1_1") (pintype "passive"))
      (node (ref "R18") (pin "1") (pinfunction "1_1") (pintype "passive"))
      (node (ref "X1") (pin "11") (pinfunction "S_11") (pintype "passive"))
    )
    (net (code "62") (name "Net-(X1D-S)") (class "Default")
      (node (ref "R19") (pin "1") (pinfunction "1_1") (pintype "passive"))
      (node (ref "R20") (pin "1") (pinfunction "1_1") (pintype "passive"))
      (node (ref "X1") (pin "12") (pinfunction "S_12") (pintype "passive"))
    )
    (net (code "63") (name "Net-(X1E-S)") (class "Default")
      (node (ref "R21") (pin "1") (pinfunction "1_1") (pintype "passive"))
      (node (ref "R22") (pin "1") (pinfunction "1_1") (pintype "passive"))
      (node (ref "X1") (pin "13") (pinfunction "S_13") (pintype "passive"))
    )
    (net (code "64") (name "Net-(X1F-S)") (class "Default")
      (node (ref "R23") (pin "1") (pinfunction "1_1") (pintype "passive"))
      (node (ref "R24") (pin "1") (pinfunction "1_1") (pintype "passive"))
      (node (ref "X1") (pin "14") (pinfunction "S_14") (pintype "passive"))
    )
    (net (code "65") (name "Net-(X1G-S)") (class "Default")
      (node (ref "R25") (pin "1") (pinfunction "1_1") (pintype "passive"))
      (node (ref "R26") (pin "1") (pinfunction "1_1") (pintype "passive"))
      (node (ref "X1") (pin "15") (pinfunction "S_15") (pintype "passive"))
    )
    (net (code "66") (name "Net-(X1H-S)") (class "Default")
      (node (ref "R27") (pin "1") (pinfunction "1_1") (pintype "passive"))
      (node (ref "R28") (pin "1") (pinfunction "1_1") (pintype "passive"))
      (node (ref "X1") (pin "16") (pinfunction "S_16") (pintype "passive"))
    )
    (net (code "67") (name "Net-(X1I-S)") (class "Default")
      (node (ref "R29") (pin "1") (pinfunction "1_1") (pintype "passive"))
      (node (ref "R30") (pin "1") (pinfunction "1_1") (pintype "passive"))
      (node (ref "X1") (pin "17") (pinfunction "S_17") (pintype "passive"))
    )
    (net (code "68") (name "Net-(X1J-S)") (class "Default")
      (node (ref "R31") (pin "1") (pinfunction "1_1") (pintype "passive"))
      (node (ref "R32") (pin "1") (pinfunction "1_1") (pintype "passive"))
      (node (ref "X1") (pin "18") (pinfunction "S_18") (pintype "passive"))
    )
    (net (code "69") (name "Net-(X1T-S)") (class "Default")
      (node (ref "R1") (pin "1") (pinfunction "1_1") (pintype "passive"))
      (node (ref "R2") (pin "1") (pinfunction "1_1") (pintype "passive"))
      (node (ref "X1") (pin "3") (pinfunction "S_3") (pintype "passive"))
    )
    (net (code "70") (name "Net-(X1U-S)") (class "Default")
      (node (ref "R3") (pin "1") (pinfunction "1_1") (pintype "passive"))
      (node (ref "R4") (pin "1") (pinfunction "1_1") (pintype "passive"))
      (node (ref "X1") (pin "4") (pinfunction "S_4") (pintype "passive"))
    )
    (net (code "71") (name "Net-(X1V-S)") (class "Default")
      (node (ref "R5") (pin "1") (pinfunction "1_1") (pintype "passive"))
      (node (ref "R6") (pin "1") (pinfunction "1_1") (pintype "passive"))
      (node (ref "X1") (pin "5") (pinfunction "S_5") (pintype "passive"))
    )
    (net (code "72") (name "Net-(X1W-S)") (class "Default")
      (node (ref "R7") (pin "1") (pinfunction "1_1") (pintype "passive"))
      (node (ref "R8") (pin "1") (pinfunction "1_1") (pintype "passive"))
      (node (ref "X1") (pin "6") (pinfunction "S_6") (pintype "passive"))
    )
    (net (code "73") (name "Net-(X1X-S)") (class "Default")
      (node (ref "R10") (pin "1") (pinfunction "1_1") (pintype "passive"))
      (node (ref "R9") (pin "1") (pinfunction "1_1") (pintype "passive"))
      (node (ref "X1") (pin "7") (pinfunction "S_7") (pintype "passive"))
    )
    (net (code "74") (name "Net-(X1Y-S)") (class "Default")
      (node (ref "R11") (pin "1") (pinfunction "1_1") (pintype "passive"))
      (node (ref "R12") (pin "1") (pinfunction "1_1") (pintype "passive"))
      (node (ref "X1") (pin "8") (pinfunction "S_8") (pintype "passive"))
    )
    (net (code "75") (name "Net-(X1Z-S)") (class "Default")
      (node (ref "R13") (pin "1") (pinfunction "1_1") (pintype "passive"))
      (node (ref "R14") (pin "1") (pinfunction "1_1") (pintype "passive"))
      (node (ref "X1") (pin "9") (pinfunction "S_9") (pintype "passive"))
    )
    (net (code "76") (name "R1") (class "Default")
      (node (ref "R1") (pin "2") (pinfunction "2_2") (pintype "passive"))
      (node (ref "U1") (pin "1") (pinfunction "A_1") (pintype "passive"))
      (node (ref "U5") (pin "15") (pinfunction "EMIT_15") (pintype "passive"))
    )
    (net (code "77") (name "R3") (class "Default")
      (node (ref "R3") (pin "2") (pinfunction "2_2") (pintype "passive"))
      (node (ref "U1") (pin "3") (pinfunction "A_3") (pintype "passive"))
      (node (ref "U5") (pin "13") (pinfunction "EMIT_13") (pintype "passive"))
    )
    (net (code "78") (name "R5") (class "Default")
      (node (ref "R5") (pin "2") (pinfunction "2_2") (pintype "passive"))
      (node (ref "U1") (pin "5") (pinfunction "A_5") (pintype "passive"))
      (node (ref "U5") (pin "11") (pinfunction "EMIT_11") (pintype "passive"))
    )
    (net (code "79") (name "R7") (class "Default")
      (node (ref "R7") (pin "2") (pinfunction "2_2") (pintype "passive"))
      (node (ref "U1") (pin "7") (pinfunction "A_7") (pintype "passive"))
      (node (ref "U5") (pin "9") (pinfunction "EMIT_9") (pintype "passive"))
    )
    (net (code "80") (name "R9") (class "Default")
      (node (ref "R9") (pin "2") (pinfunction "2_2") (pintype "passive"))
      (node (ref "U2") (pin "1") (pinfunction "A_1") (pintype "passive"))
      (node (ref "U6") (pin "15") (pinfunction "EMIT_15") (pintype "passive"))
    )
    (net (code "81") (name "R11") (class "Default")
      (node (ref "R11") (pin "2") (pinfunction "2_2") (pintype "passive"))
      (node (ref "U2") (pin "3") (pinfunction "A_3") (pintype "passive"))
      (node (ref "U6") (pin "13") (pinfunction "EMIT_13") (pintype "passive"))
    )
    (net (code "82") (name "R13") (class "Default")
      (node (ref "R13") (pin "2") (pinfunction "2_2") (pintype "passive"))
      (node (ref "U2") (pin "5") (pinfunction "A_5") (pintype "passive"))
      (node (ref "U6") (pin "11") (pinfunction "EMIT_11") (pintype "passive"))
    )
    (net (code "83") (name "R15") (class "Default")
      (node (ref "R15") (pin "2") (pinfunction "2_2") (pintype "passive"))
      (node (ref "U2") (pin "7") (pinfunction "A_7") (pintype "passive"))
      (node (ref "U6") (pin "9") (pinfunction "EMIT_9") (pintype "passive"))
    )
    (net (code "84") (name "R17") (class "Default")
      (node (ref "R17") (pin "2") (pinfunction "2_2") (pintype "passive"))
      (node (ref "U3") (pin "1") (pinfunction "A_1") (pintype "passive"))
      (node (ref "U7") (pin "15") (pinfunction "EMIT_15") (pintype "passive"))
    )
    (net (code "85") (name "R19") (class "Default")
      (node (ref "R19") (pin "2") (pinfunction "2_2") (pintype "passive"))
      (node (ref "U3") (pin "3") (pinfunction "A_3") (pintype "passive"))
      (node (ref "U7") (pin "13") (pinfunction "EMIT_13") (pintype "passive"))
    )
    (net (code "86") (name "R21") (class "Default")
      (node (ref "R21") (pin "2") (pinfunction "2_2") (pintype "passive"))
      (node (ref "U3") (pin "5") (pinfunction "A_5") (pintype "passive"))
      (node (ref "U7") (pin "11") (pinfunction "EMIT_11") (pintype "passive"))
    )
    (net (code "87") (name "R23") (class "Default")
      (node (ref "R23") (pin "2") (pinfunction "2_2") (pintype "passive"))
      (node (ref "U3") (pin "7") (pinfunction "A_7") (pintype "passive"))
      (node (ref "U7") (pin "9") (pinfunction "EMIT_9") (pintype "passive"))
    )
    (net (code "88") (name "R25") (class "Default")
      (node (ref "R25") (pin "2") (pinfunction "2_2") (pintype "passive"))
      (node (ref "U4") (pin "1") (pinfunction "A_1") (pintype "passive"))
      (node (ref "U8") (pin "15") (pinfunction "EMIT_15") (pintype "passive"))
    )
    (net (code "89") (name "R27") (class "Default")
      (node (ref "R27") (pin "2") (pinfunction "2_2") (pintype "passive"))
      (node (ref "U4") (pin "3") (pinfunction "A_3") (pintype "passive"))
      (node (ref "U8") (pin "13") (pinfunction "EMIT_13") (pintype "passive"))
    )
    (net (code "90") (name "R29") (class "Default")
      (node (ref "R29") (pin "2") (pinfunction "2_2") (pintype "passive"))
      (node (ref "U4") (pin "5") (pinfunction "A_5") (pintype "passive"))
      (node (ref "U8") (pin "11") (pinfunction "EMIT_11") (pintype "passive"))
    )
    (net (code "91") (name "R31") (class "Default")
      (node (ref "R31") (pin "2") (pinfunction "2_2") (pintype "passive"))
      (node (ref "U4") (pin "7") (pinfunction "A_7") (pintype "passive"))
      (node (ref "U8") (pin "9") (pinfunction "EMIT_9") (pintype "passive"))
    )
    (net (code "92") (name "SCL") (class "Default")
      (node (ref "IC1") (pin "12") (pinfunction "SCL_12") (pintype "input"))
      (node (ref "IOX1") (pin "5") (pinfunction "S_5") (pintype "passive"))
      (node (ref "IOX2") (pin "5") (pinfunction "S_5") (pintype "passive"))
      (node (ref "R78") (pin "2") (pinfunction "2_2") (pintype "passive"))
    )
    (net (code "93") (name "SDA") (class "Default")
      (node (ref "IC1") (pin "13") (pinfunction "SDA_13") (pintype "bidirectional"))
      (node (ref "IOX1") (pin "6") (pinfunction "S_6") (pintype "passive"))
      (node (ref "IOX2") (pin "6") (pinfunction "S_6") (pintype "passive"))
      (node (ref "R77") (pin "2") (pinfunction "2_2") (pintype "passive"))
    )
    (net (code "94") (name "VDD") (class "Default")
      (node (ref "C1") (pin "1") (pinfunction "1_1") (pintype "passive"))
      (node (ref "C3") (pin "+") (pinfunction "+_+") (pintype "passive"))
      (node (ref "IC1") (pin "9") (pinfunction "VDD_9") (pintype "power_in"))
      (node (ref "JP1") (pin "1") (pinfunction "1_1") (pintype "passive"))
      (node (ref "JP1") (pin "2") (pinfunction "2_2") (pintype "passive"))
      (node (ref "R50") (pin "2") (pinfunction "2_2") (pintype "passive"))
      (node (ref "R51") (pin "1") (pinfunction "1_1") (pintype "passive"))
      (node (ref "R52") (pin "1") (pinfunction "1_1") (pintype "passive"))
      (node (ref "R53") (pin "1") (pinfunction "1_1") (pintype "passive"))
      (node (ref "R57") (pin "1") (pinfunction "1_1") (pintype "passive"))
      (node (ref "R58") (pin "1") (pinfunction "1_1") (pintype "passive"))
      (node (ref "R59") (pin "1") (pinfunction "1_1") (pintype "passive"))
      (node (ref "R60") (pin "1") (pinfunction "1_1") (pintype "passive"))
      (node (ref "R77") (pin "1") (pinfunction "1_1") (pintype "passive"))
      (node (ref "R78") (pin "1") (pinfunction "1_1") (pintype "passive"))
      (node (ref "U1") (pin "10") (pinfunction "COL_10") (pintype "passive"))
      (node (ref "U1") (pin "12") (pinfunction "COL_12") (pintype "passive"))
      (node (ref "U1") (pin "14") (pinfunction "COL_14") (pintype "passive"))
      (node (ref "U1") (pin "16") (pinfunction "COL_16") (pintype "passive"))
      (node (ref "U2") (pin "10") (pinfunction "COL_10") (pintype "passive"))
      (node (ref "U2") (pin "12") (pinfunction "COL_12") (pintype "passive"))
      (node (ref "U2") (pin "14") (pinfunction "COL_14") (pintype "passive"))
      (node (ref "U2") (pin "16") (pinfunction "COL_16") (pintype "passive"))
      (node (ref "U3") (pin "10") (pinfunction "COL_10") (pintype "passive"))
      (node (ref "U3") (pin "12") (pinfunction "COL_12") (pintype "passive"))
      (node (ref "U3") (pin "14") (pinfunction "COL_14") (pintype "passive"))
      (node (ref "U3") (pin "16") (pinfunction "COL_16") (pintype "passive"))
      (node (ref "U4") (pin "10") (pinfunction "COL_10") (pintype "passive"))
      (node (ref "U4") (pin "12") (pinfunction "COL_12") (pintype "passive"))
      (node (ref "U4") (pin "14") (pinfunction "COL_14") (pintype "passive"))
      (node (ref "U4") (pin "16") (pinfunction "COL_16") (pintype "passive"))
    )
    (net (code "95") (name "VSS") (class "Default")
      (node (ref "C1") (pin "2") (pinfunction "2_2") (pintype "passive"))
      (node (ref "C3") (pin "-") (pinfunction "-_-") (pintype "passive"))
      (node (ref "IC1") (pin "10") (pinfunction "VSS_10") (pintype "power_in"))
      (node (ref "IOX1") (pin "2") (pinfunction "S_2") (pintype "passive"))
      (node (ref "IOX1") (pin "4") (pinfunction "S_4") (pintype "passive"))
      (node (ref "IOX2") (pin "2") (pinfunction "S_2") (pintype "passive"))
      (node (ref "IOX2") (pin "4") (pinfunction "S_4") (pintype "passive"))
      (node (ref "JP1") (pin "3") (pinfunction "3_3") (pintype "passive"))
      (node (ref "JP1") (pin "4") (pinfunction "4_4") (pintype "passive"))
      (node (ref "R34") (pin "1") (pinfunction "1_1") (pintype "passive"))
      (node (ref "R35") (pin "1") (pinfunction "1_1") (pintype "passive"))
      (node (ref "R36") (pin "1") (pinfunction "1_1") (pintype "passive"))
      (node (ref "R37") (pin "1") (pinfunction "1_1") (pintype "passive"))
      (node (ref "R38") (pin "1") (pinfunction "1_1") (pintype "passive"))
      (node (ref "R39") (pin "1") (pinfunction "1_1") (pintype "passive"))
      (node (ref "R40") (pin "1") (pinfunction "1_1") (pintype "passive"))
      (node (ref "R41") (pin "1") (pinfunction "1_1") (pintype "passive"))
      (node (ref "R42") (pin "1") (pinfunction "1_1") (pintype "passive"))
      (node (ref "R43") (pin "1") (pinfunction "1_1") (pintype "passive"))
      (node (ref "R44") (pin "1") (pinfunction "1_1") (pintype "passive"))
      (node (ref "R45") (pin "1") (pinfunction "1_1") (pintype "passive"))
      (node (ref "R46") (pin "1") (pinfunction "1_1") (pintype "passive"))
      (node (ref "R47") (pin "1") (pinfunction "1_1") (pintype "passive"))
      (node (ref "R48") (pin "1") (pinfunction "1_1") (pintype "passive"))
      (node (ref "R49") (pin "1") (pinfunction "1_1") (pintype "passive"))
      (node (ref "R54") (pin "1") (pinfunction "1_1") (pintype "passive"))
      (node (ref "R55") (pin "1") (pinfunction "1_1") (pintype "passive"))
      (node (ref "R56") (pin "1") (pinfunction "1_1") (pintype "passive"))
      (node (ref "U5") (pin "2") (pinfunction "C_2") (pintype "passive"))
      (node (ref "U5") (pin "4") (pinfunction "C_4") (pintype "passive"))
      (node (ref "U5") (pin "6") (pinfunction "C_6") (pintype "passive"))
      (node (ref "U5") (pin "8") (pinfunction "C_8") (pintype "passive"))
      (node (ref "U6") (pin "2") (pinfunction "C_2") (pintype "passive"))
      (node (ref "U6") (pin "4") (pinfunction "C_4") (pintype "passive"))
      (node (ref "U6") (pin "6") (pinfunction "C_6") (pintype "passive"))
      (node (ref "U6") (pin "8") (pinfunction "C_8") (pintype "passive"))
      (node (ref "U7") (pin "2") (pinfunction "C_2") (pintype "passive"))
      (node (ref "U7") (pin "4") (pinfunction "C_4") (pintype "passive"))
      (node (ref "U7") (pin "6") (pinfunction "C_6") (pintype "passive"))
      (node (ref "U7") (pin "8") (pinfunction "C_8") (pintype "passive"))
      (node (ref "U8") (pin "2") (pinfunction "C_2") (pintype "passive"))
      (node (ref "U8") (pin "4") (pinfunction "C_4") (pintype "passive"))
      (node (ref "U8") (pin "6") (pinfunction "C_6") (pintype "passive"))
      (node (ref "U8") (pin "8") (pinfunction "C_8") (pintype "passive"))
    )
    (net (code "96") (name "unconnected-(IC1-INTA-Pad20)") (class "Default")
      (node (ref "IC1") (pin "20") (pinfunction "INTA_20") (pintype "output"))
    )
    (net (code "97") (name "unconnected-(IC1-INTB-Pad19)") (class "Default")
      (node (ref "IC1") (pin "19") (pinfunction "INTB_19") (pintype "output"))
    )
    (net (code "98") (name "unconnected-(IOX1B-S-Pad10)") (class "Default")
      (node (ref "IOX1") (pin "10") (pinfunction "S_10") (pintype "passive"))
    )
    (net (code "99") (name "unconnected-(IOX1I-S-Pad8)") (class "Default")
      (node (ref "IOX1") (pin "8") (pinfunction "S_8") (pintype "passive"))
    )
    (net (code "100") (name "unconnected-(IOX1J-S-Pad9)") (class "Default")
      (node (ref "IOX1") (pin "9") (pinfunction "S_9") (pintype "passive"))
    )
    (net (code "101") (name "unconnected-(IOX2B-S-Pad10)") (class "Default")
      (node (ref "IOX2") (pin "10") (pinfunction "S_10") (pintype "passive"))
    )
    (net (code "102") (name "unconnected-(IOX2I-S-Pad8)") (class "Default")
      (node (ref "IOX2") (pin "8") (pinfunction "S_8") (pintype "passive"))
    )
    (net (code "103") (name "unconnected-(IOX2J-S-Pad9)") (class "Default")
      (node (ref "IOX2") (pin "9") (pinfunction "S_9") (pintype "passive"))
    )
    (net (code "104") (name "unconnected-(X1K-S-Pad19)") (class "Default")
      (node (ref "X1") (pin "19") (pinfunction "S_19") (pintype "passive"))
    )
    (net (code "105") (name "unconnected-(X1M-S-Pad20)") (class "Default")
      (node (ref "X1") (pin "20") (pinfunction "S_20") (pintype "passive"))
    )
    (net (code "106") (name "unconnected-(X1N-S-Pad21)") (class "Default")
      (node (ref "X1") (pin "21") (pinfunction "S_21") (pintype "passive"))
    )
    (net (code "107") (name "unconnected-(X1O-S-Pad22)") (class "Default")
      (node (ref "X1") (pin "22") (pinfunction "S_22") (pintype "passive"))
    )
    (net (code "108") (name "unconnected-(X1P-S-Pad23)") (class "Default")
      (node (ref "X1") (pin "23") (pinfunction "S_23") (pintype "passive"))
    )
    (net (code "109") (name "unconnected-(X1Q-S-Pad24)") (class "Default")
      (node (ref "X1") (pin "24") (pinfunction "S_24") (pintype "passive"))
    )
    (net (code "110") (name "unconnected-(X1R-S-Pad25)") (class "Default")
      (node (ref "X1") (pin "25") (pinfunction "S_25") (pintype "passive"))
    )
    (net (code "111") (name "unconnected-(X1S-S-Pad26)") (class "Default")
      (node (ref "X1") (pin "26") (pinfunction "S_26") (pintype "passive"))
    )
  )
)
